# OSO-MISC-20-021_Loggy_Board_for_Ring.net
KiCad netlist of a schematic drawn in EAGLE
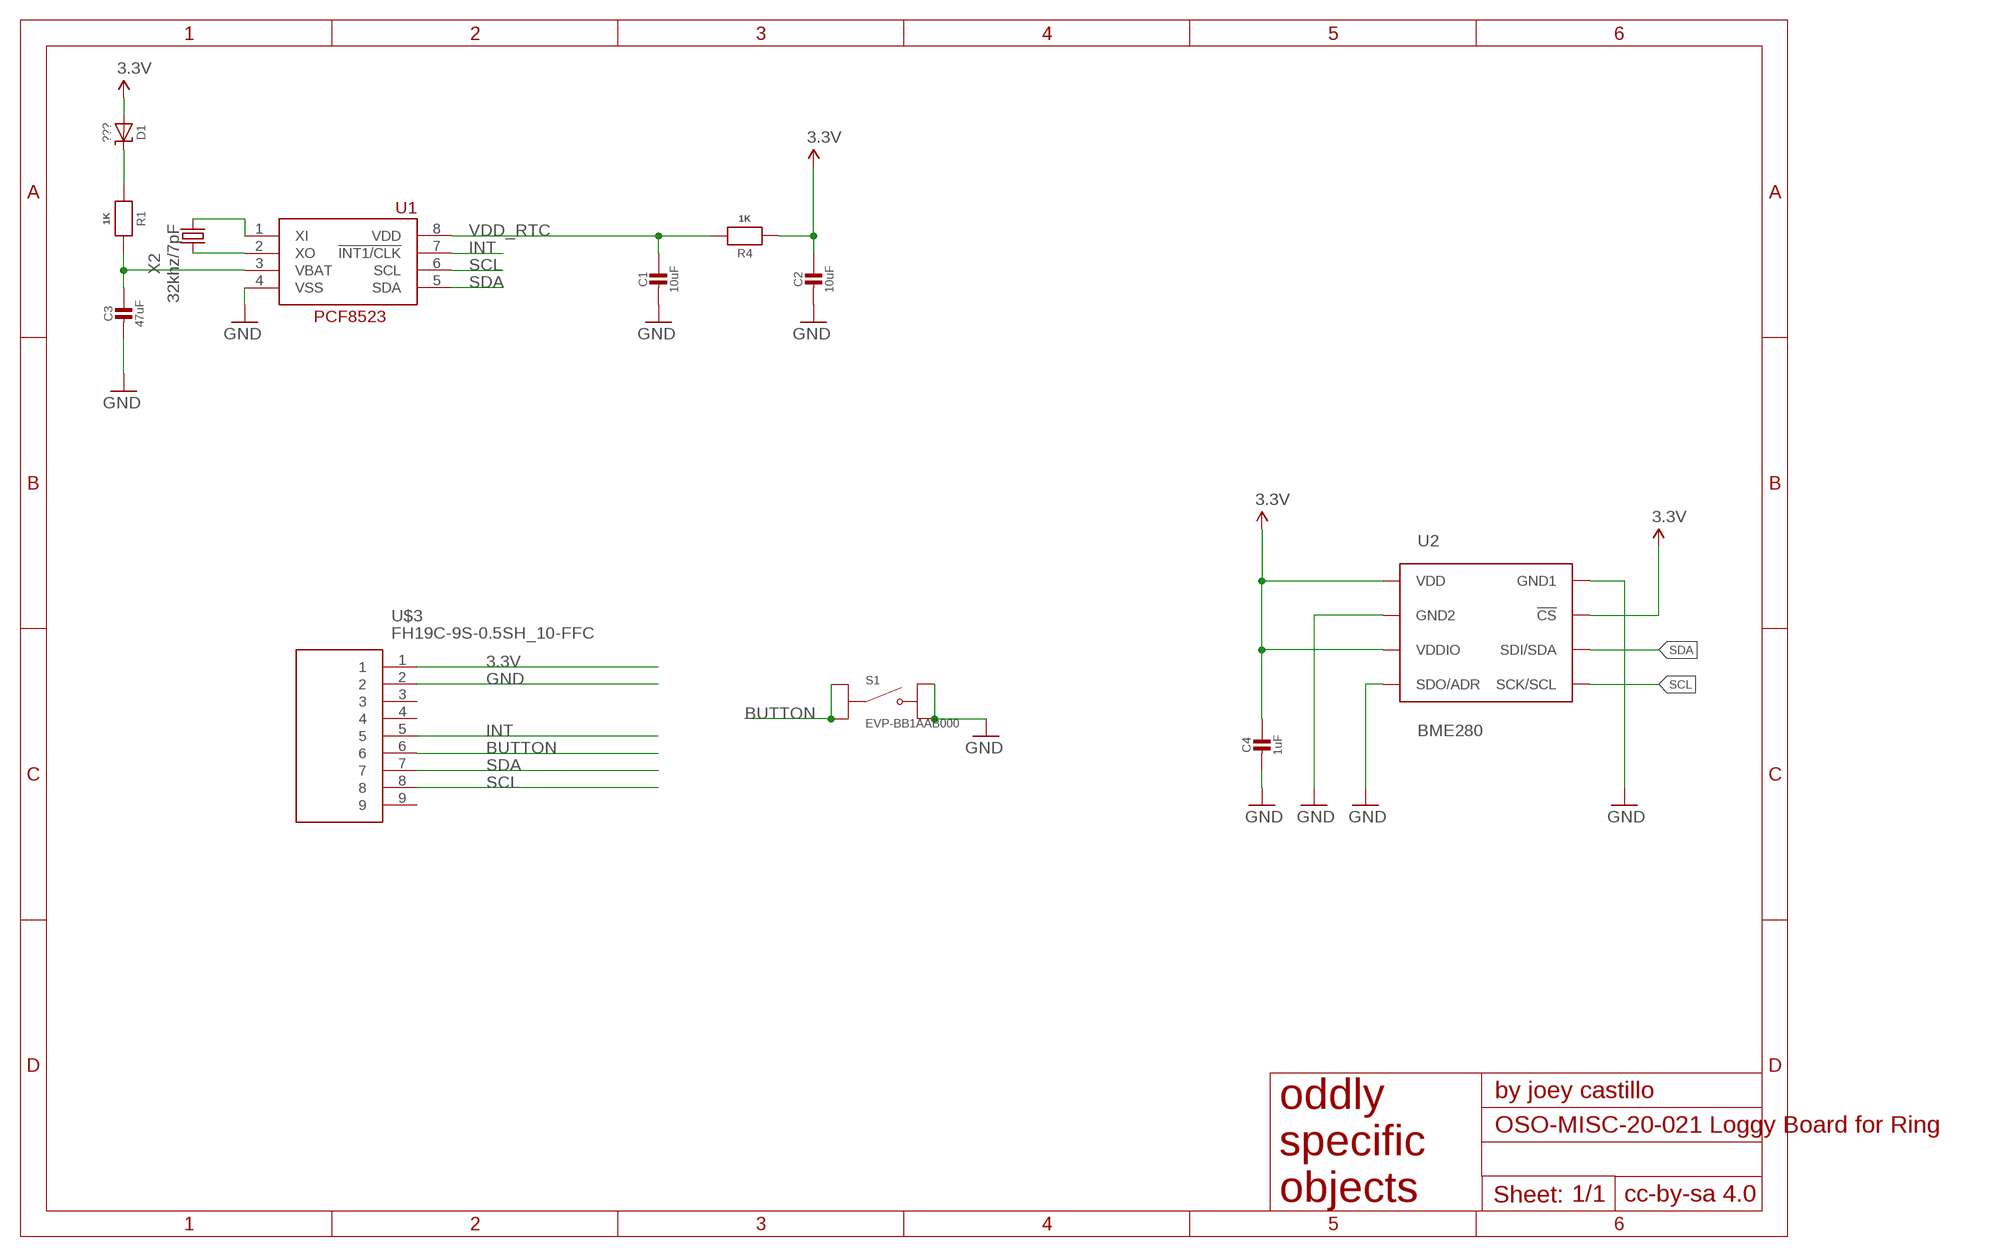
[diagram p0: schematic, sheet 1]

(export (version "E")
  (design (tool "Eeschema 10.0.6"))
  (components
    (comp (ref "C1")
      (value "10uF")
      (footprint "eagle-import:0805-NO")
      (libsource (lib "eagle-import") (part "CAP_CERAMIC0805-NOOUTLINE"))
    )
    (comp (ref "C2")
      (value "10uF")
      (footprint "eagle-import:0805-NO")
      (libsource (lib "eagle-import") (part "CAP_CERAMIC0805-NOOUTLINE"))
    )
    (comp (ref "C3")
      (value "47uF")
      (footprint "eagle-import:0805-NO")
      (libsource (lib "eagle-import") (part "CAP_CERAMIC0805-NOOUTLINE"))
    )
    (comp (ref "C4")
      (value "1uF")
      (footprint "eagle-import:_0805MP")
      (libsource (lib "eagle-import") (part "CAP_CERAMIC_0805MP"))
    )
    (comp (ref "D1")
      (value "???")
      (footprint "eagle-import:SOD-123")
      (libsource (lib "eagle-import") (part "DIODE-SCHOTTKYSOD-123"))
    )
    (comp (ref "R1")
      (value "1K")
      (footprint "eagle-import:0805-NO")
      (libsource (lib "eagle-import") (part "RESISTOR0805_NOOUTLINE"))
    )
    (comp (ref "R4")
      (value "1K")
      (footprint "eagle-import:0805-NO")
      (libsource (lib "eagle-import") (part "RESISTOR0805_NOOUTLINE"))
    )
    (comp (ref "S1")
      (value "EVP-BB1AAB000")
      (footprint "eagle-import:SW_EVP-BB1AAB000")
      (fields
        (field (name "DIGI-KEY_PART_NUMBER") "P124390CT-ND")
        (field (name "MF") "Panasonic Electronic Components")
      )
      (libsource (lib "eagle-import") (part "EVP-BB1AAB000"))
    )
    (comp (ref "U$3")
      (value "FH19C-9S-0.5SH_10-FFC")
      (footprint "eagle-import:FH19C9S05SH10-FFC")
      (libsource (lib "eagle-import") (part "FH19C-9S-0.5SH_10-FFC"))
    )
    (comp (ref "U1")
      (value "PCF8523T")
      (footprint "eagle-import:SOIC8_150MIL")
      (libsource (lib "eagle-import") (part "RTC_PCF8523T"))
    )
    (comp (ref "U2")
      (value "BME280")
      (footprint "eagle-import:BME280_LGA")
      (libsource (lib "eagle-import") (part "BME280"))
    )
    (comp (ref "X2")
      (value "32khz/7pF")
      (footprint "eagle-import:XTAL-7015")
      (libsource (lib "eagle-import") (part "CRYSTAL7015"))
    )
  )
  (nets
    (net (code "1") (name "/BUTTON") (class "Default")
      (node (ref "S1") (pin "A1") (pinfunction "A1_A1") (pintype "passive"))
      (node (ref "S1") (pin "A2") (pinfunction "A2_A2") (pintype "passive"))
      (node (ref "U$3") (pin "6") (pinfunction "6_6") (pintype "bidirectional"))
    )
    (net (code "2") (name "/INT") (class "Default")
      (node (ref "U$3") (pin "5") (pinfunction "5_5") (pintype "bidirectional"))
      (node (ref "U1") (pin "7") (pinfunction "~{INT1/CLK}_7") (pintype "output"))
    )
    (net (code "3") (name "/VDD_RTC") (class "Default")
      (node (ref "C1") (pin "1") (pinfunction "1_1") (pintype "passive"))
      (node (ref "R4") (pin "2") (pinfunction "2_2") (pintype "passive"))
      (node (ref "U1") (pin "8") (pinfunction "VDD_8") (pintype "power_in"))
    )
    (net (code "4") (name "3.3V") (class "Default")
      (node (ref "C2") (pin "1") (pinfunction "1_1") (pintype "passive"))
      (node (ref "C4") (pin "1") (pinfunction "1_1") (pintype "passive"))
      (node (ref "D1") (pin "A") (pinfunction "A_A") (pintype "passive"))
      (node (ref "R4") (pin "1") (pinfunction "1_1") (pintype "passive"))
      (node (ref "U$3") (pin "1") (pinfunction "1_1") (pintype "bidirectional"))
      (node (ref "U2") (pin "P$2") (pinfunction "~{CS}_P$2") (pintype "bidirectional"))
      (node (ref "U2") (pin "P$6") (pinfunction "VDDIO_P$6") (pintype "bidirectional"))
      (node (ref "U2") (pin "P$8") (pinfunction "VDD_P$8") (pintype "bidirectional"))
    )
    (net (code "5") (name "GND") (class "Default")
      (node (ref "C1") (pin "2") (pinfunction "2_2") (pintype "passive"))
      (node (ref "C2") (pin "2") (pinfunction "2_2") (pintype "passive"))
      (node (ref "C3") (pin "2") (pinfunction "2_2") (pintype "passive"))
      (node (ref "C4") (pin "2") (pinfunction "2_2") (pintype "passive"))
      (node (ref "S1") (pin "B1") (pinfunction "B1_B1") (pintype "passive"))
      (node (ref "S1") (pin "B2") (pinfunction "B2_B2") (pintype "passive"))
      (node (ref "U$3") (pin "2") (pinfunction "2_2") (pintype "bidirectional"))
      (node (ref "U1") (pin "4") (pinfunction "VSS_4") (pintype "power_in"))
      (node (ref "U2") (pin "P$1") (pinfunction "GND1_P$1") (pintype "bidirectional"))
      (node (ref "U2") (pin "P$5") (pinfunction "SDO/ADR_P$5") (pintype "bidirectional"))
      (node (ref "U2") (pin "P$7") (pinfunction "GND2_P$7") (pintype "bidirectional"))
    )
    (net (code "6") (name "Net-(D1-PadC)") (class "Default")
      (node (ref "D1") (pin "C") (pinfunction "C_C") (pintype "passive"))
      (node (ref "R1") (pin "1") (pinfunction "1_1") (pintype "passive"))
    )
    (net (code "7") (name "Net-(U1-VBAT)") (class "Default")
      (node (ref "C3") (pin "1") (pinfunction "1_1") (pintype "passive"))
      (node (ref "R1") (pin "2") (pinfunction "2_2") (pintype "passive"))
      (node (ref "U1") (pin "3") (pinfunction "VBAT_3") (pintype "power_in"))
    )
    (net (code "8") (name "Net-(U1-XI)") (class "Default")
      (node (ref "U1") (pin "1") (pinfunction "XI_1") (pintype "input"))
      (node (ref "X2") (pin "1") (pinfunction "1_1") (pintype "passive"))
    )
    (net (code "9") (name "Net-(U1-XO)") (class "Default")
      (node (ref "U1") (pin "2") (pinfunction "XO_2") (pintype "output"))
      (node (ref "X2") (pin "4") (pinfunction "2_4") (pintype "passive"))
    )
    (net (code "10") (name "SCL") (class "Default")
      (node (ref "U$3") (pin "8") (pinfunction "8_8") (pintype "bidirectional"))
      (node (ref "U1") (pin "6") (pinfunction "SCL_6") (pintype "bidirectional"))
      (node (ref "U2") (pin "P$4") (pinfunction "SCK/SCL_P$4") (pintype "bidirectional"))
    )
    (net (code "11") (name "SDA") (class "Default")
      (node (ref "U$3") (pin "7") (pinfunction "7_7") (pintype "bidirectional"))
      (node (ref "U1") (pin "5") (pinfunction "SDA_5") (pintype "bidirectional"))
      (node (ref "U2") (pin "P$3") (pinfunction "SDI/SDA_P$3") (pintype "bidirectional"))
    )
    (net (code "12") (name "unconnected-(U$3-Pad3)") (class "Default")
      (node (ref "U$3") (pin "3") (pinfunction "3_3") (pintype "bidirectional"))
    )
    (net (code "13") (name "unconnected-(U$3-Pad4)") (class "Default")
      (node (ref "U$3") (pin "4") (pinfunction "4_4") (pintype "bidirectional"))
    )
    (net (code "14") (name "unconnected-(U$3-Pad9)") (class "Default")
      (node (ref "U$3") (pin "9") (pinfunction "9_9") (pintype "bidirectional"))
    )
  )
)
